# SCH_Altium_OpenComs_ABP1_Front-panel.net
KiCad netlist of a schematic drawn in Altium Designer
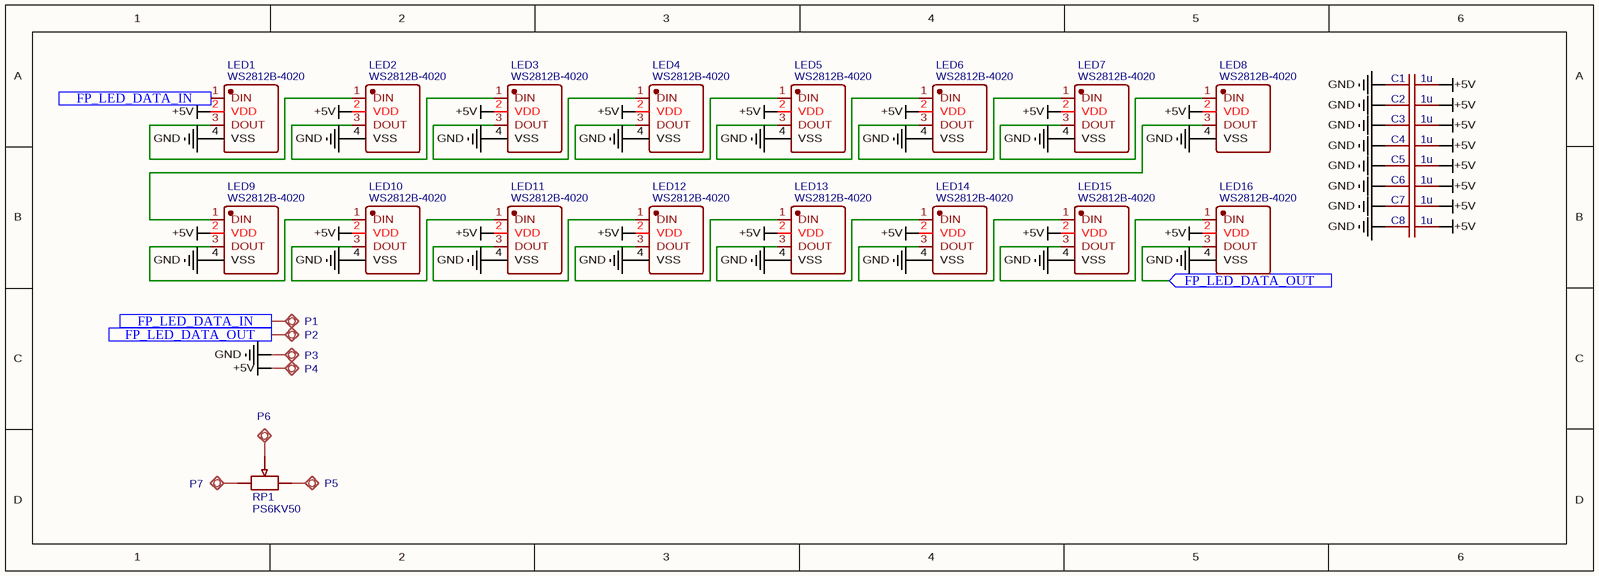
[diagram p0: SCH_Altium_OpenComs_ABP1_Front-panel_.schdoc]

(export (version "E")
  (design (tool "Eeschema 10.0.6"))
  (components
    (comp (ref "C1")
      (value "1u")
      (fields
        (field (name "BOM_SUPPLIER PART") "C28323")
        (field (name "BOM_MANUFACTURER PART") "CL21B105KBFNNNE")
        (field (name "CONTRIBUTOR") "LCEDA_Lib")
      )
      (libsource (lib "altium-import") (part "root_0_1u_"))
    )
    (comp (ref "C2")
      (value "1u")
      (fields
        (field (name "BOM_SUPPLIER PART") "C28323")
        (field (name "BOM_MANUFACTURER PART") "CL21B105KBFNNNE")
        (field (name "CONTRIBUTOR") "LCEDA_Lib")
      )
      (libsource (lib "altium-import") (part "root_0_1u_"))
    )
    (comp (ref "C3")
      (value "1u")
      (fields
        (field (name "BOM_SUPPLIER PART") "C28323")
        (field (name "BOM_MANUFACTURER PART") "CL21B105KBFNNNE")
        (field (name "CONTRIBUTOR") "LCEDA_Lib")
      )
      (libsource (lib "altium-import") (part "root_0_1u_"))
    )
    (comp (ref "C4")
      (value "1u")
      (fields
        (field (name "BOM_SUPPLIER PART") "C28323")
        (field (name "BOM_MANUFACTURER PART") "CL21B105KBFNNNE")
        (field (name "CONTRIBUTOR") "LCEDA_Lib")
      )
      (libsource (lib "altium-import") (part "root_0_1u_"))
    )
    (comp (ref "C5")
      (value "1u")
      (fields
        (field (name "BOM_SUPPLIER PART") "C28323")
        (field (name "BOM_MANUFACTURER PART") "CL21B105KBFNNNE")
        (field (name "CONTRIBUTOR") "LCEDA_Lib")
      )
      (libsource (lib "altium-import") (part "root_0_1u_"))
    )
    (comp (ref "C6")
      (value "1u")
      (fields
        (field (name "BOM_SUPPLIER PART") "C28323")
        (field (name "BOM_MANUFACTURER PART") "CL21B105KBFNNNE")
        (field (name "CONTRIBUTOR") "LCEDA_Lib")
      )
      (libsource (lib "altium-import") (part "root_0_1u_"))
    )
    (comp (ref "C7")
      (value "1u")
      (fields
        (field (name "BOM_SUPPLIER PART") "C28323")
        (field (name "BOM_MANUFACTURER PART") "CL21B105KBFNNNE")
        (field (name "CONTRIBUTOR") "LCEDA_Lib")
      )
      (libsource (lib "altium-import") (part "root_0_1u_"))
    )
    (comp (ref "C8")
      (value "1u")
      (fields
        (field (name "BOM_SUPPLIER PART") "C28323")
        (field (name "BOM_MANUFACTURER PART") "CL21B105KBFNNNE")
        (field (name "CONTRIBUTOR") "LCEDA_Lib")
      )
      (libsource (lib "altium-import") (part "root_0_1u_"))
    )
    (comp (ref "LED1")
      (value "WS2812B-4020")
      (fields (field (name "BOM_SUPPLIER PART") "C965557") (field (name "CONTRIBUTOR") "LCSC"))
      (libsource (lib "altium-import") (part "root_0_WS2812B-4020_"))
    )
    (comp (ref "LED2")
      (value "WS2812B-4020")
      (fields (field (name "BOM_SUPPLIER PART") "C965557") (field (name "CONTRIBUTOR") "LCSC"))
      (libsource (lib "altium-import") (part "root_0_WS2812B-4020_"))
    )
    (comp (ref "LED3")
      (value "WS2812B-4020")
      (fields (field (name "BOM_SUPPLIER PART") "C965557") (field (name "CONTRIBUTOR") "LCSC"))
      (libsource (lib "altium-import") (part "root_0_WS2812B-4020_"))
    )
    (comp (ref "LED4")
      (value "WS2812B-4020")
      (fields (field (name "BOM_SUPPLIER PART") "C965557") (field (name "CONTRIBUTOR") "LCSC"))
      (libsource (lib "altium-import") (part "root_0_WS2812B-4020_"))
    )
    (comp (ref "LED5")
      (value "WS2812B-4020")
      (fields (field (name "BOM_SUPPLIER PART") "C965557") (field (name "CONTRIBUTOR") "LCSC"))
      (libsource (lib "altium-import") (part "root_0_WS2812B-4020_"))
    )
    (comp (ref "LED6")
      (value "WS2812B-4020")
      (fields (field (name "BOM_SUPPLIER PART") "C965557") (field (name "CONTRIBUTOR") "LCSC"))
      (libsource (lib "altium-import") (part "root_0_WS2812B-4020_"))
    )
    (comp (ref "LED7")
      (value "WS2812B-4020")
      (fields (field (name "BOM_SUPPLIER PART") "C965557") (field (name "CONTRIBUTOR") "LCSC"))
      (libsource (lib "altium-import") (part "root_0_WS2812B-4020_"))
    )
    (comp (ref "LED8")
      (value "WS2812B-4020")
      (fields (field (name "BOM_SUPPLIER PART") "C965557") (field (name "CONTRIBUTOR") "LCSC"))
      (libsource (lib "altium-import") (part "root_0_WS2812B-4020_"))
    )
    (comp (ref "LED9")
      (value "WS2812B-4020")
      (fields (field (name "BOM_SUPPLIER PART") "C965557") (field (name "CONTRIBUTOR") "LCSC"))
      (libsource (lib "altium-import") (part "root_0_WS2812B-4020_"))
    )
    (comp (ref "LED10")
      (value "WS2812B-4020")
      (fields (field (name "BOM_SUPPLIER PART") "C965557") (field (name "CONTRIBUTOR") "LCSC"))
      (libsource (lib "altium-import") (part "root_0_WS2812B-4020_"))
    )
    (comp (ref "LED11")
      (value "WS2812B-4020")
      (fields (field (name "BOM_SUPPLIER PART") "C965557") (field (name "CONTRIBUTOR") "LCSC"))
      (libsource (lib "altium-import") (part "root_0_WS2812B-4020_"))
    )
    (comp (ref "LED12")
      (value "WS2812B-4020")
      (fields (field (name "BOM_SUPPLIER PART") "C965557") (field (name "CONTRIBUTOR") "LCSC"))
      (libsource (lib "altium-import") (part "root_0_WS2812B-4020_"))
    )
    (comp (ref "LED13")
      (value "WS2812B-4020")
      (fields (field (name "BOM_SUPPLIER PART") "C965557") (field (name "CONTRIBUTOR") "LCSC"))
      (libsource (lib "altium-import") (part "root_0_WS2812B-4020_"))
    )
    (comp (ref "LED14")
      (value "WS2812B-4020")
      (fields (field (name "BOM_SUPPLIER PART") "C965557") (field (name "CONTRIBUTOR") "LCSC"))
      (libsource (lib "altium-import") (part "root_0_WS2812B-4020_"))
    )
    (comp (ref "LED15")
      (value "WS2812B-4020")
      (fields (field (name "BOM_SUPPLIER PART") "C965557") (field (name "CONTRIBUTOR") "LCSC"))
      (libsource (lib "altium-import") (part "root_0_WS2812B-4020_"))
    )
    (comp (ref "LED16")
      (value "WS2812B-4020")
      (fields (field (name "BOM_SUPPLIER PART") "C965557") (field (name "CONTRIBUTOR") "LCSC"))
      (libsource (lib "altium-import") (part "root_0_WS2812B-4020_"))
    )
    (comp (ref "P1")
      (value "TESTPAD50")
      (fields (field (name "CONTRIBUTOR") "radiofm"))
      (libsource (lib "altium-import") (part "root_1_TESTPAD50_"))
    )
    (comp (ref "P2")
      (value "TESTPAD50")
      (fields (field (name "CONTRIBUTOR") "radiofm"))
      (libsource (lib "altium-import") (part "root_1_TESTPAD50_"))
    )
    (comp (ref "P3")
      (value "TESTPAD50")
      (fields (field (name "CONTRIBUTOR") "radiofm"))
      (libsource (lib "altium-import") (part "root_1_TESTPAD50_"))
    )
    (comp (ref "P4")
      (value "TESTPAD50")
      (fields (field (name "CONTRIBUTOR") "radiofm"))
      (libsource (lib "altium-import") (part "root_1_TESTPAD50_"))
    )
    (comp (ref "P5")
      (value "TESTPAD50")
      (fields (field (name "CONTRIBUTOR") "radiofm"))
      (libsource (lib "altium-import") (part "root_1_TESTPAD50_"))
    )
    (comp (ref "P6")
      (value "TESTPAD50")
      (fields (field (name "CONTRIBUTOR") "radiofm"))
      (libsource (lib "altium-import") (part "root_2_TESTPAD50_"))
    )
    (comp (ref "P7")
      (value "TESTPAD50")
      (fields (field (name "CONTRIBUTOR") "radiofm"))
      (libsource (lib "altium-import") (part "root_3_TESTPAD50_"))
    )
    (comp (ref "RP1")
      (value "PS6KV50")
      (fields
        (field (name "BOM_MANUFACTURER PART") "PS6KV50-103A3030-I-PM")
        (field (name "BOM_SUPPLIER PART") "PS6KV50-103A-I-PM")
        (field (name "CONTRIBUTOR") "ViperPiz")
      )
      (libsource (lib "altium-import") (part "root_0_PS6KV50_"))
    )
  )
  (nets
    (net (code "1") (name "+5V") (class "Default")
      (node (ref "C1") (pin "2") (pinfunction "2_2") (pintype "passive"))
      (node (ref "C2") (pin "2") (pinfunction "2_2") (pintype "passive"))
      (node (ref "C3") (pin "2") (pinfunction "2_2") (pintype "passive"))
      (node (ref "C4") (pin "2") (pinfunction "2_2") (pintype "passive"))
      (node (ref "C5") (pin "2") (pinfunction "2_2") (pintype "passive"))
      (node (ref "C6") (pin "2") (pinfunction "2_2") (pintype "passive"))
      (node (ref "C7") (pin "2") (pinfunction "2_2") (pintype "passive"))
      (node (ref "C8") (pin "2") (pinfunction "2_2") (pintype "passive"))
      (node (ref "LED1") (pin "2") (pinfunction "VDD_2") (pintype "passive"))
      (node (ref "LED10") (pin "2") (pinfunction "VDD_2") (pintype "passive"))
      (node (ref "LED11") (pin "2") (pinfunction "VDD_2") (pintype "passive"))
      (node (ref "LED12") (pin "2") (pinfunction "VDD_2") (pintype "passive"))
      (node (ref "LED13") (pin "2") (pinfunction "VDD_2") (pintype "passive"))
      (node (ref "LED14") (pin "2") (pinfunction "VDD_2") (pintype "passive"))
      (node (ref "LED15") (pin "2") (pinfunction "VDD_2") (pintype "passive"))
      (node (ref "LED16") (pin "2") (pinfunction "VDD_2") (pintype "passive"))
      (node (ref "LED2") (pin "2") (pinfunction "VDD_2") (pintype "passive"))
      (node (ref "LED3") (pin "2") (pinfunction "VDD_2") (pintype "passive"))
      (node (ref "LED4") (pin "2") (pinfunction "VDD_2") (pintype "passive"))
      (node (ref "LED5") (pin "2") (pinfunction "VDD_2") (pintype "passive"))
      (node (ref "LED6") (pin "2") (pinfunction "VDD_2") (pintype "passive"))
      (node (ref "LED7") (pin "2") (pinfunction "VDD_2") (pintype "passive"))
      (node (ref "LED8") (pin "2") (pinfunction "VDD_2") (pintype "passive"))
      (node (ref "LED9") (pin "2") (pinfunction "VDD_2") (pintype "passive"))
      (node (ref "P4") (pin "1") (pinfunction "PP_1") (pintype "passive"))
    )
    (net (code "2") (name "/FP_LED_DATA_IN") (class "Default")
      (node (ref "LED1") (pin "1") (pinfunction "DIN_1") (pintype "passive"))
      (node (ref "P1") (pin "1") (pinfunction "PP_1") (pintype "passive"))
    )
    (net (code "3") (name "/FP_LED_DATA_OUT") (class "Default")
      (node (ref "LED16") (pin "3") (pinfunction "DOUT_3") (pintype "passive"))
      (node (ref "P2") (pin "1") (pinfunction "PP_1") (pintype "passive"))
    )
    (net (code "4") (name "GND") (class "Default")
      (node (ref "C1") (pin "1") (pinfunction "1_1") (pintype "passive"))
      (node (ref "C2") (pin "1") (pinfunction "1_1") (pintype "passive"))
      (node (ref "C3") (pin "1") (pinfunction "1_1") (pintype "passive"))
      (node (ref "C4") (pin "1") (pinfunction "1_1") (pintype "passive"))
      (node (ref "C5") (pin "1") (pinfunction "1_1") (pintype "passive"))
      (node (ref "C6") (pin "1") (pinfunction "1_1") (pintype "passive"))
      (node (ref "C7") (pin "1") (pinfunction "1_1") (pintype "passive"))
      (node (ref "C8") (pin "1") (pinfunction "1_1") (pintype "passive"))
      (node (ref "LED1") (pin "4") (pinfunction "VSS_4") (pintype "passive"))
      (node (ref "LED10") (pin "4") (pinfunction "VSS_4") (pintype "passive"))
      (node (ref "LED11") (pin "4") (pinfunction "VSS_4") (pintype "passive"))
      (node (ref "LED12") (pin "4") (pinfunction "VSS_4") (pintype "passive"))
      (node (ref "LED13") (pin "4") (pinfunction "VSS_4") (pintype "passive"))
      (node (ref "LED14") (pin "4") (pinfunction "VSS_4") (pintype "passive"))
      (node (ref "LED15") (pin "4") (pinfunction "VSS_4") (pintype "passive"))
      (node (ref "LED16") (pin "4") (pinfunction "VSS_4") (pintype "passive"))
      (node (ref "LED2") (pin "4") (pinfunction "VSS_4") (pintype "passive"))
      (node (ref "LED3") (pin "4") (pinfunction "VSS_4") (pintype "passive"))
      (node (ref "LED4") (pin "4") (pinfunction "VSS_4") (pintype "passive"))
      (node (ref "LED5") (pin "4") (pinfunction "VSS_4") (pintype "passive"))
      (node (ref "LED6") (pin "4") (pinfunction "VSS_4") (pintype "passive"))
      (node (ref "LED7") (pin "4") (pinfunction "VSS_4") (pintype "passive"))
      (node (ref "LED8") (pin "4") (pinfunction "VSS_4") (pintype "passive"))
      (node (ref "LED9") (pin "4") (pinfunction "VSS_4") (pintype "passive"))
      (node (ref "P3") (pin "1") (pinfunction "PP_1") (pintype "passive"))
    )
    (net (code "5") (name "Net-(LED1-DOUT)") (class "Default")
      (node (ref "LED1") (pin "3") (pinfunction "DOUT_3") (pintype "passive"))
      (node (ref "LED2") (pin "1") (pinfunction "DIN_1") (pintype "passive"))
    )
    (net (code "6") (name "Net-(LED2-DOUT)") (class "Default")
      (node (ref "LED2") (pin "3") (pinfunction "DOUT_3") (pintype "passive"))
      (node (ref "LED3") (pin "1") (pinfunction "DIN_1") (pintype "passive"))
    )
    (net (code "7") (name "Net-(LED3-DOUT)") (class "Default")
      (node (ref "LED3") (pin "3") (pinfunction "DOUT_3") (pintype "passive"))
      (node (ref "LED4") (pin "1") (pinfunction "DIN_1") (pintype "passive"))
    )
    (net (code "8") (name "Net-(LED4-DOUT)") (class "Default")
      (node (ref "LED4") (pin "3") (pinfunction "DOUT_3") (pintype "passive"))
      (node (ref "LED5") (pin "1") (pinfunction "DIN_1") (pintype "passive"))
    )
    (net (code "9") (name "Net-(LED5-DOUT)") (class "Default")
      (node (ref "LED5") (pin "3") (pinfunction "DOUT_3") (pintype "passive"))
      (node (ref "LED6") (pin "1") (pinfunction "DIN_1") (pintype "passive"))
    )
    (net (code "10") (name "Net-(LED6-DOUT)") (class "Default")
      (node (ref "LED6") (pin "3") (pinfunction "DOUT_3") (pintype "passive"))
      (node (ref "LED7") (pin "1") (pinfunction "DIN_1") (pintype "passive"))
    )
    (net (code "11") (name "Net-(LED7-DOUT)") (class "Default")
      (node (ref "LED7") (pin "3") (pinfunction "DOUT_3") (pintype "passive"))
      (node (ref "LED8") (pin "1") (pinfunction "DIN_1") (pintype "passive"))
    )
    (net (code "12") (name "Net-(LED8-DOUT)") (class "Default")
      (node (ref "LED8") (pin "3") (pinfunction "DOUT_3") (pintype "passive"))
      (node (ref "LED9") (pin "1") (pinfunction "DIN_1") (pintype "passive"))
    )
    (net (code "13") (name "Net-(LED10-DIN)") (class "Default")
      (node (ref "LED10") (pin "1") (pinfunction "DIN_1") (pintype "passive"))
      (node (ref "LED9") (pin "3") (pinfunction "DOUT_3") (pintype "passive"))
    )
    (net (code "14") (name "Net-(LED10-DOUT)") (class "Default")
      (node (ref "LED10") (pin "3") (pinfunction "DOUT_3") (pintype "passive"))
      (node (ref "LED11") (pin "1") (pinfunction "DIN_1") (pintype "passive"))
    )
    (net (code "15") (name "Net-(LED11-DOUT)") (class "Default")
      (node (ref "LED11") (pin "3") (pinfunction "DOUT_3") (pintype "passive"))
      (node (ref "LED12") (pin "1") (pinfunction "DIN_1") (pintype "passive"))
    )
    (net (code "16") (name "Net-(LED12-DOUT)") (class "Default")
      (node (ref "LED12") (pin "3") (pinfunction "DOUT_3") (pintype "passive"))
      (node (ref "LED13") (pin "1") (pinfunction "DIN_1") (pintype "passive"))
    )
    (net (code "17") (name "Net-(LED13-DOUT)") (class "Default")
      (node (ref "LED13") (pin "3") (pinfunction "DOUT_3") (pintype "passive"))
      (node (ref "LED14") (pin "1") (pinfunction "DIN_1") (pintype "passive"))
    )
    (net (code "18") (name "Net-(LED14-DOUT)") (class "Default")
      (node (ref "LED14") (pin "3") (pinfunction "DOUT_3") (pintype "passive"))
      (node (ref "LED15") (pin "1") (pinfunction "DIN_1") (pintype "passive"))
    )
    (net (code "19") (name "Net-(LED15-DOUT)") (class "Default")
      (node (ref "LED15") (pin "3") (pinfunction "DOUT_3") (pintype "passive"))
      (node (ref "LED16") (pin "1") (pinfunction "DIN_1") (pintype "passive"))
    )
    (net (code "20") (name "Net-(P5-PP)") (class "Default")
      (node (ref "P5") (pin "1") (pinfunction "PP_1") (pintype "passive"))
      (node (ref "RP1") (pin "3") (pinfunction "3_3") (pintype "passive"))
    )
    (net (code "21") (name "Net-(P6-PP)") (class "Default")
      (node (ref "P6") (pin "1") (pinfunction "PP_1") (pintype "passive"))
      (node (ref "RP1") (pin "2") (pinfunction "2_2") (pintype "passive"))
    )
    (net (code "22") (name "Net-(P7-PP)") (class "Default")
      (node (ref "P7") (pin "1") (pinfunction "PP_1") (pintype "passive"))
      (node (ref "RP1") (pin "1") (pinfunction "1_1") (pintype "passive"))
    )
  )
)
